# Main.net
KiCad netlist of a schematic drawn in Altium Designer
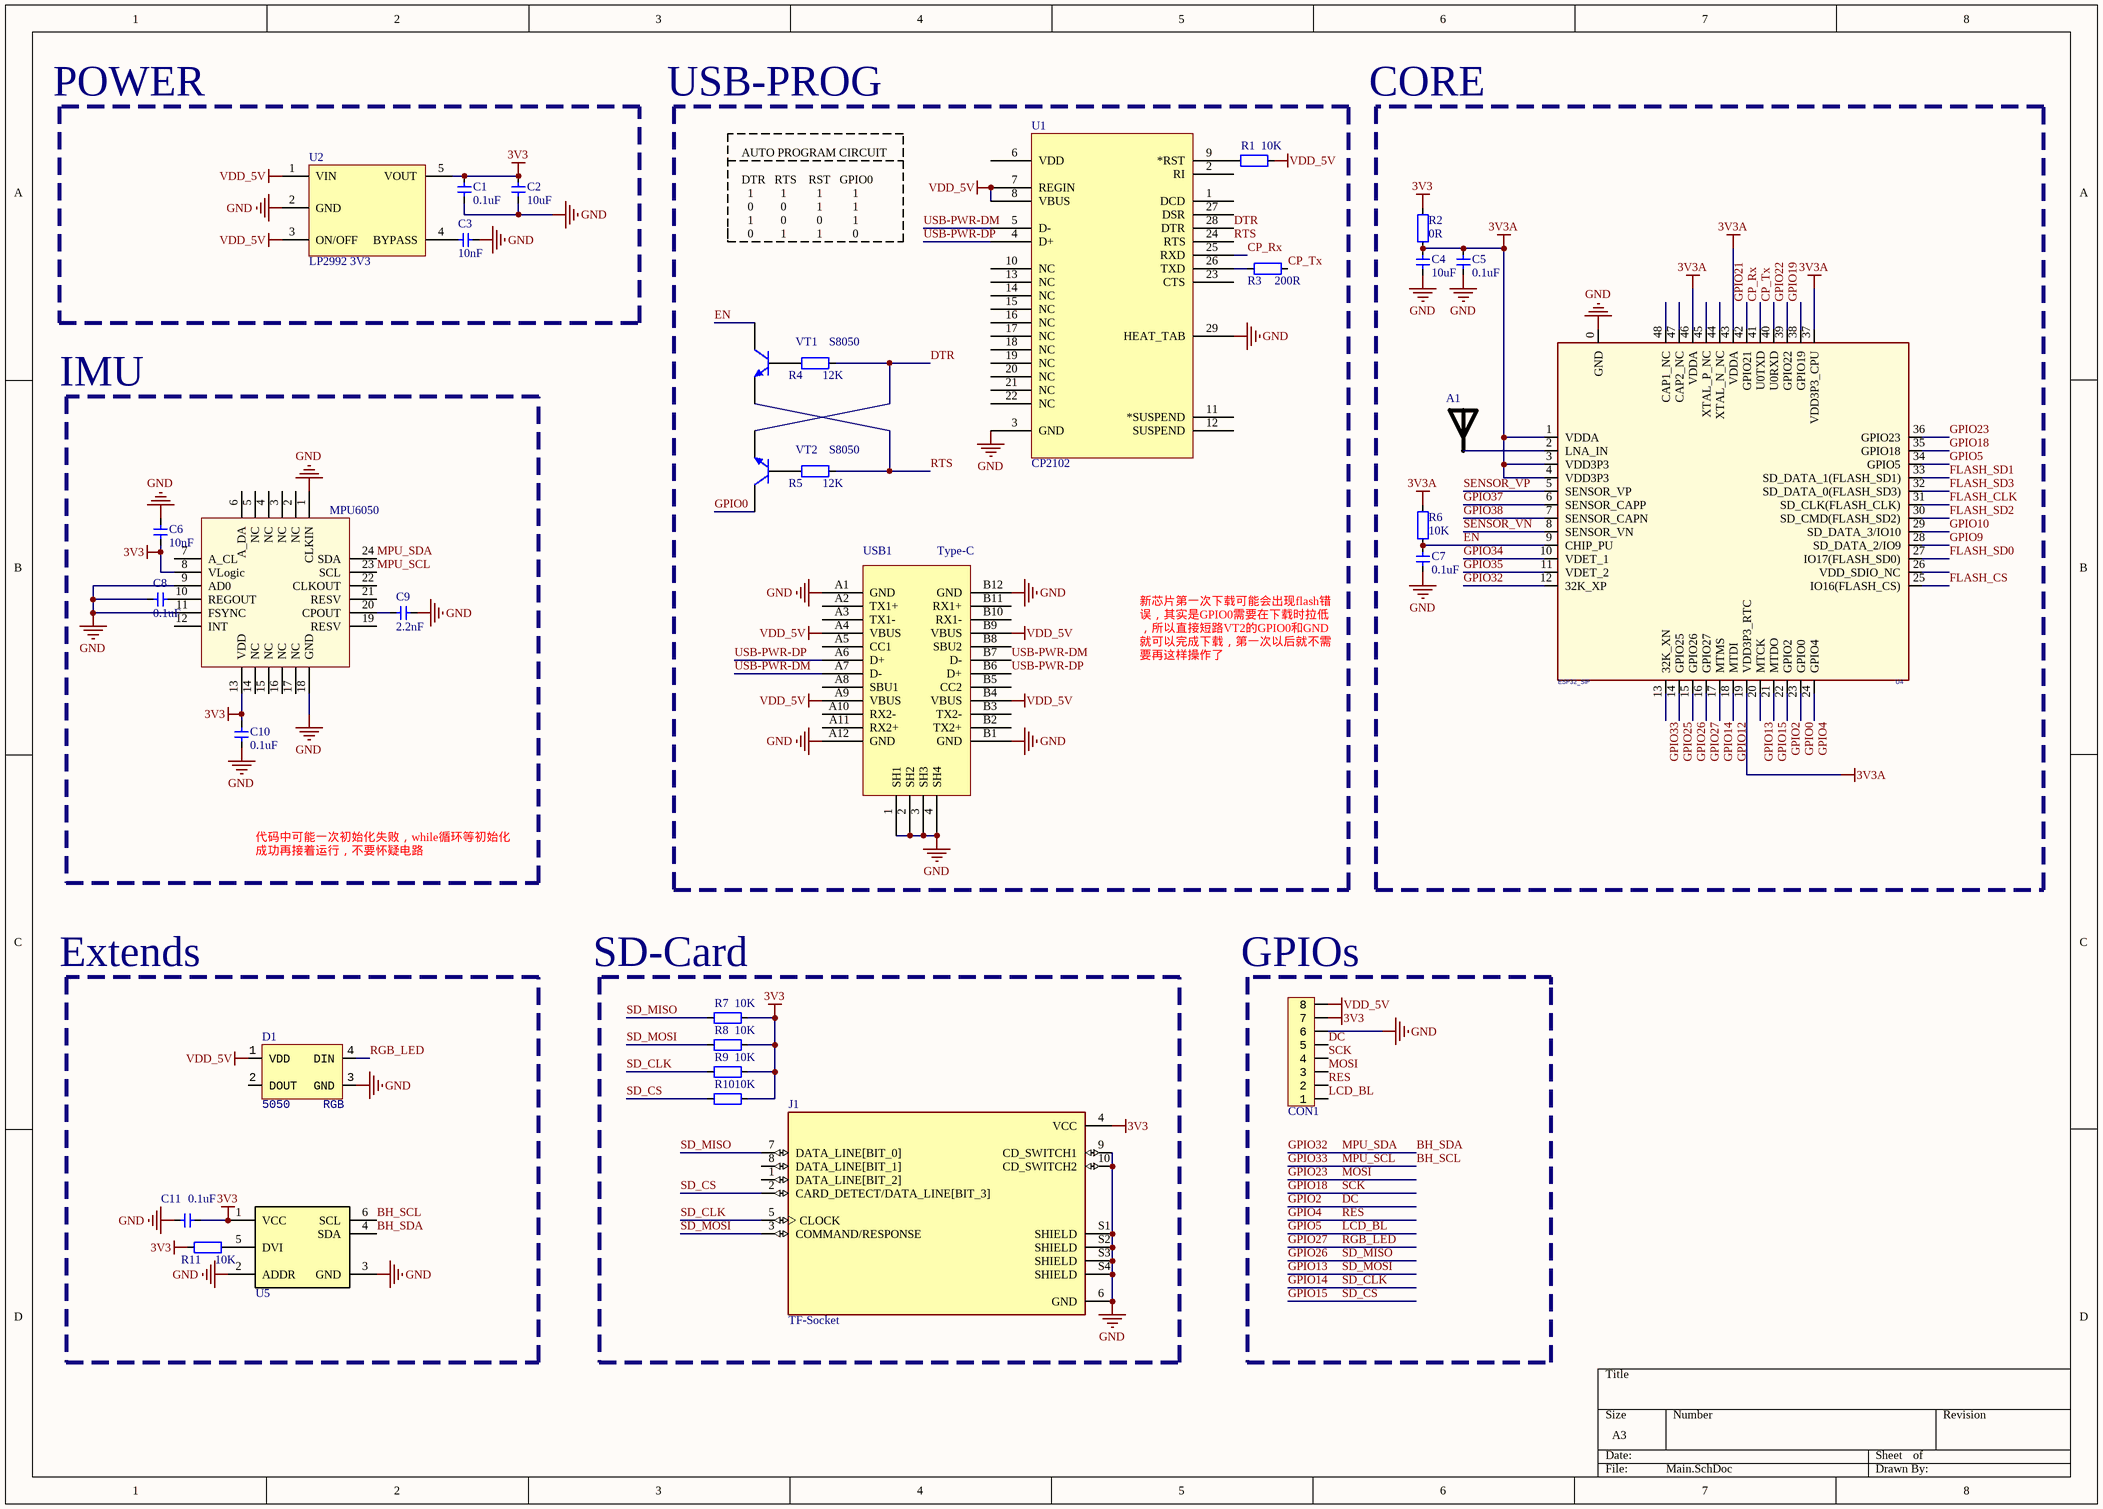
[diagram p0: Main.SchDoc]

(export (version "E")
  (design (tool "Eeschema 10.0.6"))
  (components
    (comp (ref "A1")
      (value "RAINSUN")
      (footprint "ANT-Rainsun-AN5120")
      (libsource (lib "MyPcbLib") (part "ANT-Rainsun-AP5120"))
    )
    (comp (ref "C1")
      (value "0.1uF")
      (footprint "CAP_0402")
      (description "Capacitor")
      (libsource (lib "MyPcbLib") (part "电容-0402"))
    )
    (comp (ref "C2")
      (value "10uF")
      (footprint "CAP_0402")
      (description "Capacitor")
      (libsource (lib "MyPcbLib") (part "电容-0402"))
    )
    (comp (ref "C3")
      (value "10nF")
      (footprint "CAP_0402")
      (description "Capacitor")
      (libsource (lib "MyPcbLib") (part "电容-0402"))
    )
    (comp (ref "C4")
      (value "10uF")
      (footprint "CAP_0402")
      (description "Capacitor")
      (libsource (lib "MyPcbLib") (part "电容-0402"))
    )
    (comp (ref "C5")
      (value "0.1uF")
      (footprint "CAP_0402")
      (description "Capacitor")
      (libsource (lib "MyPcbLib") (part "电容-0402"))
    )
    (comp (ref "C6")
      (value "10nF")
      (footprint "CAP_0402")
      (description "Capacitor")
      (libsource (lib "MyPcbLib") (part "电容-0402"))
    )
    (comp (ref "C7")
      (value "0.1uF")
      (footprint "CAP_0402")
      (description "Capacitor")
      (libsource (lib "MyPcbLib") (part "电容-0402"))
    )
    (comp (ref "C8")
      (value "0.1uF")
      (footprint "CAP_0402")
      (description "Capacitor")
      (libsource (lib "MyPcbLib") (part "电容-0402"))
    )
    (comp (ref "C9")
      (value "2.2nF")
      (footprint "CAP_0402")
      (description "Capacitor")
      (libsource (lib "MyPcbLib") (part "电容-0402"))
    )
    (comp (ref "C10")
      (value "0.1uF")
      (footprint "CAP_0402")
      (description "Capacitor")
      (libsource (lib "MyPcbLib") (part "电容-0402"))
    )
    (comp (ref "C11")
      (value "0.1uF")
      (footprint "CAP_0402")
      (description "Capacitor")
      (libsource (lib "MyPcbLib") (part "电容-0402"))
    )
    (comp (ref "CON1")
      (value "FFC_0.5_8")
      (footprint "FFC_0.5_8")
      (description "FFC")
      (libsource (lib "KitSprout") (part "FFC_0.5_8"))
    )
    (comp (ref "D1")
      (value "RGB")
      (footprint "LED_5050_WS2812B")
      (description "LED")
      (fields (field (name "TYPE") "5050"))
      (libsource (lib "KitSprout") (part "LED_5050_WS2812B"))
    )
    (comp (ref "J1")
      (value "TF-Socket")
      (footprint "TF-Card-Amphenol with TF")
      (description "10 _8 + 2_ Position Card Connector Secure Digital - microSDâ„¢ Surface Mount, Right Angle Gold")
      (fields (field (name "MP") "1140084168") (field (name "MF") "Amphenol Commercial Products"))
      (libsource (lib "MyPcbLib") (part "TF-Socket"))
    )
    (comp (ref "R1")
      (value "10K")
      (footprint "RES_0402")
      (description "Resistor")
      (libsource (lib "MyPcbLib") (part "电阻-0402"))
    )
    (comp (ref "R2")
      (value "0R")
      (footprint "RES_0402")
      (description "Resistor")
      (libsource (lib "") (part "电阻-0402_1"))
    )
    (comp (ref "R3")
      (value "200R")
      (footprint "RES_0402")
      (description "Resistor")
      (libsource (lib "MyPcbLib") (part "电阻-0402"))
    )
    (comp (ref "R4")
      (value "12K")
      (footprint "RES_0402")
      (description "Resistor")
      (libsource (lib "MyPcbLib") (part "电阻-0402"))
    )
    (comp (ref "R5")
      (value "12K")
      (footprint "RES_0402")
      (description "Resistor")
      (libsource (lib "MyPcbLib") (part "电阻-0402"))
    )
    (comp (ref "R6")
      (value "10K")
      (footprint "RES_0402")
      (description "Resistor")
      (libsource (lib "") (part "电阻-0402_1"))
    )
    (comp (ref "R7")
      (value "10K")
      (footprint "RES_0402")
      (description "Resistor")
      (libsource (lib "MyPcbLib") (part "电阻-0402"))
    )
    (comp (ref "R8")
      (value "10K")
      (footprint "RES_0402")
      (description "Resistor")
      (libsource (lib "MyPcbLib") (part "电阻-0402"))
    )
    (comp (ref "R9")
      (value "10K")
      (footprint "RES_0402")
      (description "Resistor")
      (libsource (lib "MyPcbLib") (part "电阻-0402"))
    )
    (comp (ref "R10")
      (value "10K")
      (footprint "RES_0402")
      (description "Resistor")
      (libsource (lib "MyPcbLib") (part "电阻-0402"))
    )
    (comp (ref "R11")
      (value "10K")
      (footprint "RES_0402")
      (description "Resistor")
      (libsource (lib "MyPcbLib") (part "电阻-0402"))
    )
    (comp (ref "U1")
      (value "CP2102")
      (footprint "QFN-28")
      (description "USB转TTL")
      (libsource (lib "mLib") (part "CP2102"))
    )
    (comp (ref "U2")
      (value "LP2992 3V3")
      (footprint "SOT23-5")
      (description "LDO")
      (libsource (lib "MyPcbLib") (part "LP2992"))
    )
    (comp (ref "U3")
      (value "MPU6050")
      (footprint "QFN-24")
      (description "六轴传感器")
      (libsource (lib "mLib") (part "MPU6050"))
    )
    (comp (ref "U4")
      (value "ESP32_SIP")
      (footprint "QFN-48_7X7")
      (libsource (lib "MyPcbLib") (part "ESP32-PICO"))
    )
    (comp (ref "U5")
      (value "BH1750FVI-TR")
      (footprint "BH1750FVI")
      (libsource (lib "MyPcbLib") (part "BH1750FVI-TR"))
    )
    (comp (ref "USB1")
      (value "Type-C")
      (footprint "Type-C-TOP")
      (libsource (lib "MyPcbLib") (part "USB-Type-C-TOP"))
    )
    (comp (ref "VT1")
      (value "S8050")
      (footprint "SMT_TRIODE_NPN")
      (description "Surface mount NPN transistor, package SOT-23")
      (libsource (lib "MyPcbLib") (part "SMT_TRIODE_NPN"))
    )
    (comp (ref "VT2")
      (value "S8050")
      (footprint "SMT_TRIODE_NPN")
      (description "Surface mount NPN transistor, package SOT-23")
      (libsource (lib "MyPcbLib") (part "SMT_TRIODE_NPN"))
    )
  )
  (nets
    (net (code "1") (name "/BH_SCL") (class "Default")
      (node (ref "U3") (pin "23") (pinfunction "SCL_23") (pintype "passive"))
      (node (ref "U4") (pin "13") (pinfunction "32K_XN_13") (pintype "passive"))
      (node (ref "U5") (pin "6") (pinfunction "SCL_6") (pintype "passive"))
    )
    (net (code "2") (name "/BH_SDA") (class "Default")
      (node (ref "U3") (pin "24") (pinfunction "SDA_24") (pintype "passive"))
      (node (ref "U4") (pin "12") (pinfunction "32K_XP_12") (pintype "passive"))
      (node (ref "U5") (pin "4") (pinfunction "SDA_4") (pintype "passive"))
    )
    (net (code "3") (name "/CP_Rx") (class "Default")
      (node (ref "U1") (pin "25") (pinfunction "RXD_25") (pintype "passive"))
      (node (ref "U4") (pin "41") (pinfunction "U0TXD_41") (pintype "power_in"))
    )
    (net (code "4") (name "/CP_Tx") (class "Default")
      (node (ref "R3") (pin "1") (pinfunction "1_1") (pintype "passive"))
      (node (ref "U4") (pin "40") (pinfunction "U0RXD_40") (pintype "power_in"))
    )
    (net (code "5") (name "/DC") (class "Default")
      (node (ref "CON1") (pin "5") (pinfunction "5_5") (pintype "passive"))
      (node (ref "U4") (pin "22") (pinfunction "GPIO2_22") (pintype "passive"))
    )
    (net (code "6") (name "/DTR") (class "Default")
      (node (ref "R4") (pin "1") (pinfunction "1_1") (pintype "passive"))
      (node (ref "U1") (pin "28") (pinfunction "DTR_28") (pintype "passive"))
      (node (ref "VT2") (pin "2") (pinfunction "E_2") (pintype "passive"))
    )
    (net (code "7") (name "/EN") (class "Default")
      (node (ref "C7") (pin "1") (pinfunction "1_1") (pintype "passive"))
      (node (ref "R6") (pin "2") (pinfunction "2_2") (pintype "passive"))
      (node (ref "U4") (pin "9") (pinfunction "CHIP_PU_9") (pintype "passive"))
      (node (ref "VT1") (pin "3") (pinfunction "C_3") (pintype "passive"))
    )
    (net (code "8") (name "/FLASH_CLK") (class "Default")
      (node (ref "U4") (pin "31") (pinfunction "SD_CLK(FLASH_CLK)_31") (pintype "passive"))
    )
    (net (code "9") (name "/FLASH_CS") (class "Default")
      (node (ref "U4") (pin "25") (pinfunction "IO16(FLASH_CS)_25") (pintype "passive"))
    )
    (net (code "10") (name "/FLASH_SD0") (class "Default")
      (node (ref "U4") (pin "27") (pinfunction "IO17(FLASH_SD0)_27") (pintype "passive"))
    )
    (net (code "11") (name "/FLASH_SD1") (class "Default")
      (node (ref "U4") (pin "33") (pinfunction "SD_DATA_1(FLASH_SD1)_33") (pintype "passive"))
    )
    (net (code "12") (name "/FLASH_SD2") (class "Default")
      (node (ref "U4") (pin "30") (pinfunction "SD_CMD(FLASH_SD2)_30") (pintype "passive"))
    )
    (net (code "13") (name "/FLASH_SD3") (class "Default")
      (node (ref "U4") (pin "32") (pinfunction "SD_DATA_0(FLASH_SD3)_32") (pintype "passive"))
    )
    (net (code "14") (name "/GPIO0") (class "Default")
      (node (ref "U4") (pin "23") (pinfunction "GPIO0_23") (pintype "passive"))
      (node (ref "VT2") (pin "3") (pinfunction "C_3") (pintype "passive"))
    )
    (net (code "15") (name "/GPIO4") (class "Default")
      (node (ref "CON1") (pin "2") (pinfunction "2_2") (pintype "passive"))
      (node (ref "U4") (pin "24") (pinfunction "GPIO4_24") (pintype "passive"))
    )
    (net (code "16") (name "/GPIO5") (class "Default")
      (node (ref "CON1") (pin "1") (pinfunction "1_1") (pintype "passive"))
      (node (ref "U4") (pin "34") (pinfunction "GPIO5_34") (pintype "passive"))
    )
    (net (code "17") (name "/GPIO9") (class "Default")
      (node (ref "U4") (pin "28") (pinfunction "SD_DATA_2/IO9_28") (pintype "passive"))
    )
    (net (code "18") (name "/GPIO10") (class "Default")
      (node (ref "U4") (pin "29") (pinfunction "SD_DATA_3/IO10_29") (pintype "passive"))
    )
    (net (code "19") (name "/GPIO12") (class "Default")
      (node (ref "U4") (pin "18") (pinfunction "MTDI_18") (pintype "passive"))
    )
    (net (code "20") (name "/GPIO13") (class "Default")
      (node (ref "J1") (pin "3") (pinfunction "COMMAND/RESPONSE_3") (pintype "bidirectional"))
      (node (ref "R8") (pin "2") (pinfunction "2_2") (pintype "passive"))
      (node (ref "U4") (pin "20") (pinfunction "MTCK_20") (pintype "passive"))
    )
    (net (code "21") (name "/GPIO14") (class "Default")
      (node (ref "J1") (pin "5") (pinfunction "CLOCK_5") (pintype "bidirectional"))
      (node (ref "R9") (pin "2") (pinfunction "2_2") (pintype "passive"))
      (node (ref "U4") (pin "17") (pinfunction "MTMS_17") (pintype "passive"))
    )
    (net (code "22") (name "/GPIO15") (class "Default")
      (node (ref "J1") (pin "2") (pinfunction "CARD_DETECT/DATA_LINE[BIT_3]_2") (pintype "bidirectional"))
      (node (ref "R10") (pin "2") (pinfunction "2_2") (pintype "passive"))
      (node (ref "U4") (pin "21") (pinfunction "MTDO_21") (pintype "passive"))
    )
    (net (code "23") (name "/GPIO18") (class "Default")
      (node (ref "CON1") (pin "4") (pinfunction "4_4") (pintype "passive"))
      (node (ref "U4") (pin "35") (pinfunction "GPIO18_35") (pintype "passive"))
    )
    (net (code "24") (name "/GPIO19") (class "Default")
      (node (ref "U4") (pin "38") (pinfunction "GPIO19_38") (pintype "passive"))
    )
    (net (code "25") (name "/GPIO21") (class "Default")
      (node (ref "U4") (pin "42") (pinfunction "GPIO21_42") (pintype "passive"))
    )
    (net (code "26") (name "/GPIO22") (class "Default")
      (node (ref "U4") (pin "39") (pinfunction "GPIO22_39") (pintype "passive"))
    )
    (net (code "27") (name "/GPIO23") (class "Default")
      (node (ref "CON1") (pin "3") (pinfunction "3_3") (pintype "passive"))
      (node (ref "U4") (pin "36") (pinfunction "GPIO23_36") (pintype "passive"))
    )
    (net (code "28") (name "/GPIO25") (class "Default")
      (node (ref "U4") (pin "14") (pinfunction "GPIO25_14") (pintype "passive"))
    )
    (net (code "29") (name "/GPIO26") (class "Default")
      (node (ref "J1") (pin "7") (pinfunction "DATA_LINE[BIT_0]_7") (pintype "bidirectional"))
      (node (ref "R7") (pin "2") (pinfunction "2_2") (pintype "passive"))
      (node (ref "U4") (pin "15") (pinfunction "GPIO26_15") (pintype "passive"))
    )
    (net (code "30") (name "/GPIO27") (class "Default")
      (node (ref "D1") (pin "4") (pinfunction "DIN_4") (pintype "passive"))
      (node (ref "U4") (pin "16") (pinfunction "GPIO27_16") (pintype "passive"))
    )
    (net (code "31") (name "/GPIO34") (class "Default")
      (node (ref "U4") (pin "10") (pinfunction "VDET_1_10") (pintype "passive"))
    )
    (net (code "32") (name "/GPIO35") (class "Default")
      (node (ref "U4") (pin "11") (pinfunction "VDET_2_11") (pintype "passive"))
    )
    (net (code "33") (name "/GPIO37") (class "Default")
      (node (ref "U4") (pin "6") (pinfunction "SENSOR_CAPP_6") (pintype "passive"))
    )
    (net (code "34") (name "/GPIO38") (class "Default")
      (node (ref "U4") (pin "7") (pinfunction "SENSOR_CAPN_7") (pintype "passive"))
    )
    (net (code "35") (name "/RTS") (class "Default")
      (node (ref "R5") (pin "1") (pinfunction "1_1") (pintype "passive"))
      (node (ref "U1") (pin "24") (pinfunction "RTS_24") (pintype "passive"))
      (node (ref "VT1") (pin "2") (pinfunction "E_2") (pintype "passive"))
    )
    (net (code "36") (name "/SENSOR_VN") (class "Default")
      (node (ref "U4") (pin "8") (pinfunction "SENSOR_VN_8") (pintype "passive"))
    )
    (net (code "37") (name "/SENSOR_VP") (class "Default")
      (node (ref "U4") (pin "5") (pinfunction "SENSOR_VP_5") (pintype "passive"))
    )
    (net (code "38") (name "/USB-PWR-DM") (class "Default")
      (node (ref "U1") (pin "5") (pinfunction "D-_5") (pintype "passive"))
      (node (ref "USB1") (pin "A7") (pinfunction "D-_A7") (pintype "passive"))
      (node (ref "USB1") (pin "B7") (pinfunction "D-_B7") (pintype "passive"))
    )
    (net (code "39") (name "/USB-PWR-DP") (class "Default")
      (node (ref "U1") (pin "4") (pinfunction "D+_4") (pintype "passive"))
      (node (ref "USB1") (pin "A6") (pinfunction "D+_A6") (pintype "passive"))
      (node (ref "USB1") (pin "B6") (pinfunction "D+_B6") (pintype "passive"))
    )
    (net (code "40") (name "3V3") (class "Default")
      (node (ref "C1") (pin "2") (pinfunction "2_2") (pintype "passive"))
      (node (ref "C10") (pin "2") (pinfunction "2_2") (pintype "passive"))
      (node (ref "C11") (pin "1") (pinfunction "1_1") (pintype "passive"))
      (node (ref "C2") (pin "2") (pinfunction "2_2") (pintype "passive"))
      (node (ref "C6") (pin "1") (pinfunction "1_1") (pintype "passive"))
      (node (ref "CON1") (pin "7") (pinfunction "7_7") (pintype "passive"))
      (node (ref "J1") (pin "4") (pinfunction "VCC_4") (pintype "power_in"))
      (node (ref "R10") (pin "1") (pinfunction "1_1") (pintype "passive"))
      (node (ref "R11") (pin "2") (pinfunction "2_2") (pintype "passive"))
      (node (ref "R2") (pin "1") (pinfunction "1_1") (pintype "passive"))
      (node (ref "R7") (pin "1") (pinfunction "1_1") (pintype "passive"))
      (node (ref "R8") (pin "1") (pinfunction "1_1") (pintype "passive"))
      (node (ref "R9") (pin "1") (pinfunction "1_1") (pintype "passive"))
      (node (ref "U2") (pin "5") (pinfunction "VOUT_5") (pintype "passive"))
      (node (ref "U3") (pin "13") (pinfunction "VDD_13") (pintype "passive"))
      (node (ref "U3") (pin "8") (pinfunction "VLogic_8") (pintype "passive"))
      (node (ref "U5") (pin "1") (pinfunction "VCC_1") (pintype "passive"))
    )
    (net (code "41") (name "3V3A") (class "Default")
      (node (ref "C4") (pin "2") (pinfunction "2_2") (pintype "passive"))
      (node (ref "C5") (pin "2") (pinfunction "2_2") (pintype "passive"))
      (node (ref "R2") (pin "2") (pinfunction "2_2") (pintype "passive"))
      (node (ref "R6") (pin "1") (pinfunction "1_1") (pintype "passive"))
      (node (ref "U4") (pin "1") (pinfunction "VDDA_1") (pintype "power_in"))
      (node (ref "U4") (pin "19") (pinfunction "VDD3P3_RTC_19") (pintype "power_in"))
      (node (ref "U4") (pin "3") (pinfunction "VDD3P3_3") (pintype "power_in"))
      (node (ref "U4") (pin "37") (pinfunction "VDD3P3_CPU_37") (pintype "power_in"))
      (node (ref "U4") (pin "4") (pinfunction "VDD3P3_4") (pintype "power_in"))
      (node (ref "U4") (pin "43") (pinfunction "VDDA_43") (pintype "power_in"))
      (node (ref "U4") (pin "46") (pinfunction "VDDA_46") (pintype "power_in"))
    )
    (net (code "42") (name "GND") (class "Default")
      (node (ref "C1") (pin "1") (pinfunction "1_1") (pintype "passive"))
      (node (ref "C10") (pin "1") (pinfunction "1_1") (pintype "passive"))
      (node (ref "C11") (pin "2") (pinfunction "2_2") (pintype "passive"))
      (node (ref "C2") (pin "1") (pinfunction "1_1") (pintype "passive"))
      (node (ref "C3") (pin "1") (pinfunction "1_1") (pintype "passive"))
      (node (ref "C4") (pin "1") (pinfunction "1_1") (pintype "passive"))
      (node (ref "C5") (pin "1") (pinfunction "1_1") (pintype "passive"))
      (node (ref "C6") (pin "2") (pinfunction "2_2") (pintype "passive"))
      (node (ref "C7") (pin "2") (pinfunction "2_2") (pintype "passive"))
      (node (ref "C8") (pin "2") (pinfunction "2_2") (pintype "passive"))
      (node (ref "C9") (pin "1") (pinfunction "1_1") (pintype "passive"))
      (node (ref "CON1") (pin "6") (pinfunction "6_6") (pintype "passive"))
      (node (ref "D1") (pin "3") (pinfunction "GND_3") (pintype "passive"))
      (node (ref "J1") (pin "10") (pinfunction "CD_SWITCH2_10") (pintype "bidirectional"))
      (node (ref "J1") (pin "6") (pinfunction "GND_6") (pintype "power_in"))
      (node (ref "J1") (pin "9") (pinfunction "CD_SWITCH1_9") (pintype "bidirectional"))
      (node (ref "J1") (pin "S1") (pinfunction "SHIELD_S1") (pintype "passive"))
      (node (ref "J1") (pin "S2") (pinfunction "SHIELD_S2") (pintype "passive"))
      (node (ref "J1") (pin "S3") (pinfunction "SHIELD_S3") (pintype "passive"))
      (node (ref "J1") (pin "S4") (pinfunction "SHIELD_S4") (pintype "passive"))
      (node (ref "U1") (pin "29") (pinfunction "HEAT_TAB_29") (pintype "passive"))
      (node (ref "U1") (pin "3") (pinfunction "GND_3") (pintype "passive"))
      (node (ref "U2") (pin "2") (pinfunction "GND_2") (pintype "passive"))
      (node (ref "U3") (pin "1") (pinfunction "CLKIN_1") (pintype "passive"))
      (node (ref "U3") (pin "11") (pinfunction "FSYNC_11") (pintype "passive"))
      (node (ref "U3") (pin "18") (pinfunction "GND_18") (pintype "passive"))
      (node (ref "U3") (pin "9") (pinfunction "AD0_9") (pintype "passive"))
      (node (ref "U4") (pin "0") (pinfunction "GND_0") (pintype "power_in"))
      (node (ref "U5") (pin "2") (pinfunction "ADDR_2") (pintype "passive"))
      (node (ref "U5") (pin "3") (pinfunction "GND_3") (pintype "passive"))
      (node (ref "USB1") (pin "1") (pinfunction "SH1_1") (pintype "passive"))
      (node (ref "USB1") (pin "2") (pinfunction "SH2_2") (pintype "passive"))
      (node (ref "USB1") (pin "3") (pinfunction "SH3_3") (pintype "passive"))
      (node (ref "USB1") (pin "4") (pinfunction "SH4_4") (pintype "passive"))
      (node (ref "USB1") (pin "A1") (pinfunction "GND_A1") (pintype "passive"))
      (node (ref "USB1") (pin "A12") (pinfunction "GND_A12") (pintype "passive"))
      (node (ref "USB1") (pin "B1") (pinfunction "GND_B1") (pintype "passive"))
      (node (ref "USB1") (pin "B12") (pinfunction "GND_B12") (pintype "passive"))
    )
    (net (code "43") (name "Net-(U1-*RST)") (class "Default")
      (node (ref "R1") (pin "2") (pinfunction "2_2") (pintype "passive"))
      (node (ref "U1") (pin "9") (pinfunction "*RST_9") (pintype "passive"))
    )
    (net (code "44") (name "Net-(U1-TXD)") (class "Default")
      (node (ref "R3") (pin "2") (pinfunction "2_2") (pintype "passive"))
      (node (ref "U1") (pin "26") (pinfunction "TXD_26") (pintype "passive"))
    )
    (net (code "45") (name "Net-(U2-BYPASS)") (class "Default")
      (node (ref "C3") (pin "2") (pinfunction "2_2") (pintype "passive"))
      (node (ref "U2") (pin "4") (pinfunction "BYPASS_4") (pintype "passive"))
    )
    (net (code "46") (name "Net-(U3-CPOUT)") (class "Default")
      (node (ref "C9") (pin "2") (pinfunction "2_2") (pintype "passive"))
      (node (ref "U3") (pin "20") (pinfunction "CPOUT_20") (pintype "passive"))
    )
    (net (code "47") (name "Net-(U3-REGOUT)") (class "Default")
      (node (ref "C8") (pin "1") (pinfunction "1_1") (pintype "passive"))
      (node (ref "U3") (pin "10") (pinfunction "REGOUT_10") (pintype "passive"))
    )
    (net (code "48") (name "Net-(U4-LNA_IN)") (class "Default")
      (node (ref "A1") (pin "1") (pinfunction "1_1") (pintype "passive"))
      (node (ref "U4") (pin "2") (pinfunction "LNA_IN_2") (pintype "passive"))
    )
    (net (code "49") (name "Net-(U5-DVI)") (class "Default")
      (node (ref "R11") (pin "1") (pinfunction "1_1") (pintype "passive"))
      (node (ref "U5") (pin "5") (pinfunction "DVI_5") (pintype "passive"))
    )
    (net (code "50") (name "Net-(VT1-B)") (class "Default")
      (node (ref "R4") (pin "2") (pinfunction "2_2") (pintype "passive"))
      (node (ref "VT1") (pin "1") (pinfunction "B_1") (pintype "passive"))
    )
    (net (code "51") (name "Net-(VT2-B)") (class "Default")
      (node (ref "R5") (pin "2") (pinfunction "2_2") (pintype "passive"))
      (node (ref "VT2") (pin "1") (pinfunction "B_1") (pintype "passive"))
    )
    (net (code "52") (name "VDD_5V") (class "Default")
      (node (ref "CON1") (pin "8") (pinfunction "8_8") (pintype "passive"))
      (node (ref "D1") (pin "1") (pinfunction "VDD_1") (pintype "passive"))
      (node (ref "R1") (pin "1") (pinfunction "1_1") (pintype "passive"))
      (node (ref "U1") (pin "7") (pinfunction "REGIN_7") (pintype "passive"))
      (node (ref "U1") (pin "8") (pinfunction "VBUS_8") (pintype "passive"))
      (node (ref "U2") (pin "1") (pinfunction "VIN_1") (pintype "passive"))
      (node (ref "U2") (pin "3") (pinfunction "ON/OFF_3") (pintype "passive"))
      (node (ref "USB1") (pin "A4") (pinfunction "VBUS_A4") (pintype "passive"))
      (node (ref "USB1") (pin "A9") (pinfunction "VBUS_A9") (pintype "passive"))
      (node (ref "USB1") (pin "B4") (pinfunction "VBUS_B4") (pintype "passive"))
      (node (ref "USB1") (pin "B9") (pinfunction "VBUS_B9") (pintype "passive"))
    )
    (net (code "53") (name "unconnected-(D1-DOUT-Pad2)") (class "Default")
      (node (ref "D1") (pin "2") (pinfunction "DOUT_2") (pintype "passive"))
    )
    (net (code "54") (name "unconnected-(J1-DATA_LINE[BIT_1]-Pad8)") (class "Default")
      (node (ref "J1") (pin "8") (pinfunction "DATA_LINE[BIT_1]_8") (pintype "bidirectional"))
    )
    (net (code "55") (name "unconnected-(J1-DATA_LINE[BIT_2]-Pad1)") (class "Default")
      (node (ref "J1") (pin "1") (pinfunction "DATA_LINE[BIT_2]_1") (pintype "bidirectional"))
    )
    (net (code "56") (name "unconnected-(U1-*SUSPEND-Pad11)") (class "Default")
      (node (ref "U1") (pin "11") (pinfunction "*SUSPEND_11") (pintype "passive"))
    )
    (net (code "57") (name "unconnected-(U1-CTS-Pad23)") (class "Default")
      (node (ref "U1") (pin "23") (pinfunction "CTS_23") (pintype "passive"))
    )
    (net (code "58") (name "unconnected-(U1-DCD-Pad1)") (class "Default")
      (node (ref "U1") (pin "1") (pinfunction "DCD_1") (pintype "passive"))
    )
    (net (code "59") (name "unconnected-(U1-DSR-Pad27)") (class "Default")
      (node (ref "U1") (pin "27") (pinfunction "DSR_27") (pintype "passive"))
    )
    (net (code "60") (name "unconnected-(U1-NC-Pad10)") (class "Default")
      (node (ref "U1") (pin "10") (pinfunction "NC_10") (pintype "passive"))
    )
    (net (code "61") (name "unconnected-(U1-NC-Pad13)") (class "Default")
      (node (ref "U1") (pin "13") (pinfunction "NC_13") (pintype "passive"))
    )
    (net (code "62") (name "unconnected-(U1-NC-Pad14)") (class "Default")
      (node (ref "U1") (pin "14") (pinfunction "NC_14") (pintype "passive"))
    )
    (net (code "63") (name "unconnected-(U1-NC-Pad15)") (class "Default")
      (node (ref "U1") (pin "15") (pinfunction "NC_15") (pintype "passive"))
    )
    (net (code "64") (name "unconnected-(U1-NC-Pad16)") (class "Default")
      (node (ref "U1") (pin "16") (pinfunction "NC_16") (pintype "passive"))
    )
    (net (code "65") (name "unconnected-(U1-NC-Pad17)") (class "Default")
      (node (ref "U1") (pin "17") (pinfunction "NC_17") (pintype "passive"))
    )
    (net (code "66") (name "unconnected-(U1-NC-Pad18)") (class "Default")
      (node (ref "U1") (pin "18") (pinfunction "NC_18") (pintype "passive"))
    )
    (net (code "67") (name "unconnected-(U1-NC-Pad19)") (class "Default")
      (node (ref "U1") (pin "19") (pinfunction "NC_19") (pintype "passive"))
    )
    (net (code "68") (name "unconnected-(U1-NC-Pad20)") (class "Default")
      (node (ref "U1") (pin "20") (pinfunction "NC_20") (pintype "passive"))
    )
    (net (code "69") (name "unconnected-(U1-NC-Pad21)") (class "Default")
      (node (ref "U1") (pin "21") (pinfunction "NC_21") (pintype "passive"))
    )
    (net (code "70") (name "unconnected-(U1-NC-Pad22)") (class "Default")
      (node (ref "U1") (pin "22") (pinfunction "NC_22") (pintype "passive"))
    )
    (net (code "71") (name "unconnected-(U1-RI-Pad2)") (class "Default")
      (node (ref "U1") (pin "2") (pinfunction "RI_2") (pintype "passive"))
    )
    (net (code "72") (name "unconnected-(U1-SUSPEND-Pad12)") (class "Default")
      (node (ref "U1") (pin "12") (pinfunction "SUSPEND_12") (pintype "passive"))
    )
    (net (code "73") (name "unconnected-(U1-VDD-Pad6)") (class "Default")
      (node (ref "U1") (pin "6") (pinfunction "VDD_6") (pintype "passive"))
    )
    (net (code "74") (name "unconnected-(U3-A_CL-Pad7)") (class "Default")
      (node (ref "U3") (pin "7") (pinfunction "A_CL_7") (pintype "passive"))
    )
    (net (code "75") (name "unconnected-(U3-A_DA-Pad6)") (class "Default")
      (node (ref "U3") (pin "6") (pinfunction "A_DA_6") (pintype "passive"))
    )
    (net (code "76") (name "unconnected-(U3-CLKOUT-Pad22)") (class "Default")
      (node (ref "U3") (pin "22") (pinfunction "CLKOUT_22") (pintype "passive"))
    )
    (net (code "77") (name "unconnected-(U3-INT-Pad12)") (class "Default")
      (node (ref "U3") (pin "12") (pinfunction "INT_12") (pintype "passive"))
    )
    (net (code "78") (name "unconnected-(U3-NC-Pad2)") (class "Default")
      (node (ref "U3") (pin "2") (pinfunction "NC_2") (pintype "passive"))
    )
    (net (code "79") (name "unconnected-(U3-NC-Pad3)") (class "Default")
      (node (ref "U3") (pin "3") (pinfunction "NC_3") (pintype "passive"))
    )
    (net (code "80") (name "unconnected-(U3-NC-Pad4)") (class "Default")
      (node (ref "U3") (pin "4") (pinfunction "NC_4") (pintype "passive"))
    )
    (net (code "81") (name "unconnected-(U3-NC-Pad5)") (class "Default")
      (node (ref "U3") (pin "5") (pinfunction "NC_5") (pintype "passive"))
    )
    (net (code "82") (name "unconnected-(U3-NC-Pad14)") (class "Default")
      (node (ref "U3") (pin "14") (pinfunction "NC_14") (pintype "passive"))
    )
    (net (code "83") (name "unconnected-(U3-NC-Pad15)") (class "Default")
      (node (ref "U3") (pin "15") (pinfunction "NC_15") (pintype "passive"))
    )
    (net (code "84") (name "unconnected-(U3-NC-Pad16)") (class "Default")
      (node (ref "U3") (pin "16") (pinfunction "NC_16") (pintype "passive"))
    )
    (net (code "85") (name "unconnected-(U3-NC-Pad17)") (class "Default")
      (node (ref "U3") (pin "17") (pinfunction "NC_17") (pintype "passive"))
    )
    (net (code "86") (name "unconnected-(U3-RESV-Pad19)") (class "Default")
      (node (ref "U3") (pin "19") (pinfunction "RESV_19") (pintype "passive"))
    )
    (net (code "87") (name "unconnected-(U3-RESV-Pad21)") (class "Default")
      (node (ref "U3") (pin "21") (pinfunction "RESV_21") (pintype "passive"))
    )
    (net (code "88") (name "unconnected-(U4-CAP1_NC-Pad48)") (class "Default")
      (node (ref "U4") (pin "48") (pinfunction "CAP1_NC_48") (pintype "passive"))
    )
    (net (code "89") (name "unconnected-(U4-CAP2_NC-Pad47)") (class "Default")
      (node (ref "U4") (pin "47") (pinfunction "CAP2_NC_47") (pintype "passive"))
    )
    (net (code "90") (name "unconnected-(U4-VDD_SDIO_NC-Pad26)") (class "Default")
      (node (ref "U4") (pin "26") (pinfunction "VDD_SDIO_NC_26") (pintype "passive"))
    )
    (net (code "91") (name "unconnected-(U4-XTAL_N_NC-Pad44)") (class "Default")
      (node (ref "U4") (pin "44") (pinfunction "XTAL_N_NC_44") (pintype "passive"))
    )
    (net (code "92") (name "unconnected-(U4-XTAL_P_NC-Pad45)") (class "Default")
      (node (ref "U4") (pin "45") (pinfunction "XTAL_P_NC_45") (pintype "passive"))
    )
    (net (code "93") (name "unconnected-(USB1-CC1-PadA5)") (class "Default")
      (node (ref "USB1") (pin "A5") (pinfunction "CC1_A5") (pintype "passive"))
    )
    (net (code "94") (name "unconnected-(USB1-CC2-PadB5)") (class "Default")
      (node (ref "USB1") (pin "B5") (pinfunction "CC2_B5") (pintype "passive"))
    )
    (net (code "95") (name "unconnected-(USB1-RX1+-PadB11)") (class "Default")
      (node (ref "USB1") (pin "B11") (pinfunction "RX1+_B11") (pintype "passive"))
    )
    (net (code "96") (name "unconnected-(USB1-RX1--PadB10)") (class "Default")
      (node (ref "USB1") (pin "B10") (pinfunction "RX1-_B10") (pintype "passive"))
    )
    (net (code "97") (name "unconnected-(USB1-RX2+-PadA11)") (class "Default")
      (node (ref "USB1") (pin "A11") (pinfunction "RX2+_A11") (pintype "passive"))
    )
    (net (code "98") (name "unconnected-(USB1-RX2--PadA10)") (class "Default")
      (node (ref "USB1") (pin "A10") (pinfunction "RX2-_A10") (pintype "passive"))
    )
    (net (code "99") (name "unconnected-(USB1-SBU1-PadA8)") (class "Default")
      (node (ref "USB1") (pin "A8") (pinfunction "SBU1_A8") (pintype "passive"))
    )
    (net (code "100") (name "unconnected-(USB1-SBU2-PadB8)") (class "Default")
      (node (ref "USB1") (pin "B8") (pinfunction "SBU2_B8") (pintype "passive"))
    )
    (net (code "101") (name "unconnected-(USB1-TX1+-PadA2)") (class "Default")
      (node (ref "USB1") (pin "A2") (pinfunction "TX1+_A2") (pintype "passive"))
    )
    (net (code "102") (name "unconnected-(USB1-TX1--PadA3)") (class "Default")
      (node (ref "USB1") (pin "A3") (pinfunction "TX1-_A3") (pintype "passive"))
    )
    (net (code "103") (name "unconnected-(USB1-TX2+-PadB2)") (class "Default")
      (node (ref "USB1") (pin "B2") (pinfunction "TX2+_B2") (pintype "passive"))
    )
    (net (code "104") (name "unconnected-(USB1-TX2--PadB3)") (class "Default")
      (node (ref "USB1") (pin "B3") (pinfunction "TX2-_B3") (pintype "passive"))
    )
  )
)
